# CATS-FAT-Pyro.net
KiCad netlist of a schematic drawn in Altium Designer
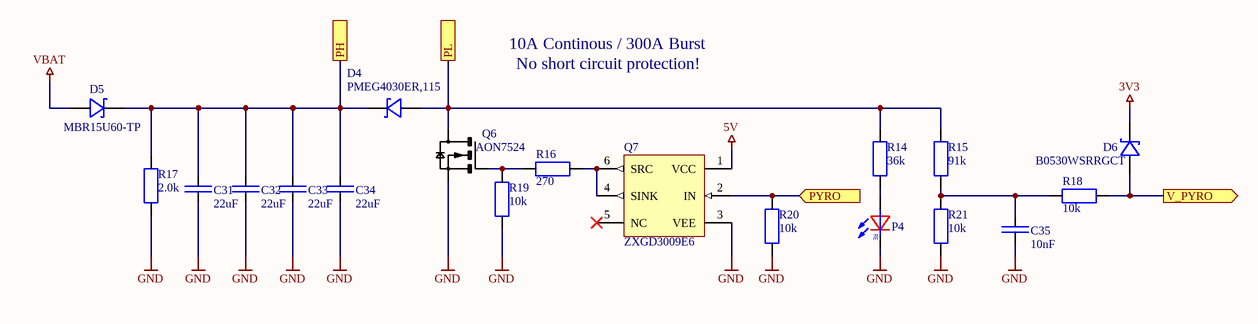
[diagram p0: CATS-FAT-Pyro.SchDoc]

(export (version "E")
  (design (tool "Eeschema 10.0.6"))
  (components
    (comp (ref "C31")
      (value "22uF")
      (footprint "SMD Keramikkondensator 0805")
      (description "SMD Ceramic Capacitor E6")
      (libsource (lib "Ceramic Capacitors-E6") (part "E6 - 22uF"))
    )
    (comp (ref "C32")
      (value "22uF")
      (footprint "SMD Keramikkondensator 0805")
      (description "SMD Ceramic Capacitor E6")
      (libsource (lib "Ceramic Capacitors-E6") (part "E6 - 22uF"))
    )
    (comp (ref "C33")
      (value "22uF")
      (footprint "SMD Keramikkondensator 0805")
      (description "SMD Ceramic Capacitor E6")
      (libsource (lib "Ceramic Capacitors-E6") (part "E6 - 22uF"))
    )
    (comp (ref "C34")
      (value "22uF")
      (footprint "SMD Keramikkondensator 0805")
      (description "SMD Ceramic Capacitor E6")
      (libsource (lib "Ceramic Capacitors-E6") (part "E6 - 22uF"))
    )
    (comp (ref "C35")
      (value "10nF")
      (footprint "SMD Keramikkondensator 0603")
      (description "SMD Ceramic Capacitor E6")
      (libsource (lib "Ceramic Capacitors-E6") (part "E6 - 10nF"))
    )
    (comp (ref "D4")
      (value "PMEG4030ER,115")
      (footprint "SMD Diode SOD-123")
      (description "Diode Schottky 3A Surface Mount CFP3")
      (libsource (lib "Diodes") (part "PMEG4030ER,115"))
    )
    (comp (ref "D5")
      (value "MBR15U60-TP")
      (footprint "SMD Diode TO-277")
      (description "Diode Schottky 15A Surface Mount TO-277-3")
      (libsource (lib "Diodes") (part "MBR15U60-TP"))
    )
    (comp (ref "D6")
      (value "B0530WSRRGCT")
      (footprint "SMD Diode SOD-323F")
      (description "200mW, 0.47V Schottky Barrier Diode")
      (libsource (lib "Diodes") (part "B0530WSRRGCT"))
    )
    (comp (ref "P4")
      (value "LED")
      (footprint "SMD LED 0603")
      (description "Color LED")
      (libsource (lib "Diodes") (part "LED"))
    )
    (comp (ref "Q6")
      (value "AON7524")
      (footprint "SMD MOSFET DFN 3x3 EP")
      (description "N-Channel 30V 25A (Ta), 28A (Tc) 3.1W (Ta), 32W (Tc) Surface Mount 8-DFN (3x3)")
      (libsource (lib "Electronic Switches") (part "AON7524"))
    )
    (comp (ref "Q7")
      (value "ZXGD3009E6")
      (footprint "SMD IC SOT-23-6")
      (description "Low-Side Gate Driver IC Non-Inverting SOT-26")
      (libsource (lib "Electronic Switches") (part "ZXGD3009E6"))
    )
    (comp (ref "R14")
      (value "36k")
      (footprint "SMD Widerstand 0603")
      (description "SMD Chip Resistor E24")
      (libsource (lib "Resistors-E24") (part "E24 - 36k"))
    )
    (comp (ref "R15")
      (value "91k")
      (footprint "SMD Widerstand 0603")
      (description "SMD Chip Resistor E24")
      (libsource (lib "Resistors-E24") (part "E24 - 91k"))
    )
    (comp (ref "R16")
      (value "270")
      (footprint "SMD Widerstand 0603")
      (description "SMD Chip Resistor E24")
      (libsource (lib "Resistors-E24") (part "E24 - 270"))
    )
    (comp (ref "R17")
      (value "2.0k")
      (footprint "SMD Widerstand 0603")
      (description "SMD Chip Resistor E24")
      (libsource (lib "Resistors-E24") (part "E24 - 2.0k"))
    )
    (comp (ref "R18")
      (value "10k")
      (footprint "SMD Widerstand 0603")
      (description "SMD Chip Resistor E24")
      (libsource (lib "Resistors-E24") (part "E24 - 10k"))
    )
    (comp (ref "R19")
      (value "10k")
      (footprint "SMD Widerstand 0603")
      (description "SMD Chip Resistor E24")
      (libsource (lib "") (part "E24 - 10k_1"))
    )
    (comp (ref "R20")
      (value "10k")
      (footprint "SMD Widerstand 0603")
      (description "SMD Chip Resistor E24")
      (libsource (lib "") (part "E24 - 10k_1"))
    )
    (comp (ref "R21")
      (value "10k")
      (footprint "SMD Widerstand 0603")
      (description "SMD Chip Resistor E24")
      (libsource (lib "") (part "E24 - 10k_1"))
    )
  )
  (nets
    (net (code "1") (name "/PH") (class "Default")
      (node (ref "C31") (pin "2") (pinfunction "2_2") (pintype "passive"))
      (node (ref "C32") (pin "2") (pinfunction "2_2") (pintype "passive"))
      (node (ref "C33") (pin "2") (pinfunction "2_2") (pintype "passive"))
      (node (ref "C34") (pin "2") (pinfunction "2_2") (pintype "passive"))
      (node (ref "D4") (pin "K") (pinfunction "K_K") (pintype "passive"))
      (node (ref "D5") (pin "K") (pinfunction "K_K") (pintype "passive"))
      (node (ref "R17") (pin "2") (pinfunction "2_2") (pintype "passive"))
    )
    (net (code "2") (name "/PL") (class "Default")
      (node (ref "D4") (pin "A") (pinfunction "A_A") (pintype "passive"))
      (node (ref "Q6") (pin "D") (pinfunction "D_D") (pintype "passive"))
      (node (ref "R14") (pin "2") (pinfunction "2_2") (pintype "passive"))
      (node (ref "R15") (pin "2") (pinfunction "2_2") (pintype "passive"))
    )
    (net (code "3") (name "/PYRO") (class "Default")
      (node (ref "Q7") (pin "2") (pinfunction "IN_2") (pintype "input"))
      (node (ref "R20") (pin "2") (pinfunction "2_2") (pintype "passive"))
    )
    (net (code "4") (name "/V_PYRO") (class "Default")
      (node (ref "D6") (pin "A") (pinfunction "A_A") (pintype "passive"))
      (node (ref "R18") (pin "1") (pinfunction "1_1") (pintype "passive"))
    )
    (net (code "5") (name "3V3") (class "Default")
      (node (ref "D6") (pin "K") (pinfunction "K_K") (pintype "passive"))
    )
    (net (code "6") (name "5V") (class "Default")
      (node (ref "Q7") (pin "1") (pinfunction "VCC_1") (pintype "passive"))
    )
    (net (code "7") (name "GND") (class "Default")
      (node (ref "C31") (pin "1") (pinfunction "1_1") (pintype "passive"))
      (node (ref "C32") (pin "1") (pinfunction "1_1") (pintype "passive"))
      (node (ref "C33") (pin "1") (pinfunction "1_1") (pintype "passive"))
      (node (ref "C34") (pin "1") (pinfunction "1_1") (pintype "passive"))
      (node (ref "C35") (pin "1") (pinfunction "1_1") (pintype "passive"))
      (node (ref "P4") (pin "K") (pinfunction "K_K") (pintype "passive"))
      (node (ref "Q6") (pin "S") (pinfunction "S_S") (pintype "passive"))
      (node (ref "Q7") (pin "3") (pinfunction "VEE_3") (pintype "passive"))
      (node (ref "R17") (pin "1") (pinfunction "1_1") (pintype "passive"))
      (node (ref "R19") (pin "1") (pinfunction "1_1") (pintype "passive"))
      (node (ref "R20") (pin "1") (pinfunction "1_1") (pintype "passive"))
      (node (ref "R21") (pin "1") (pinfunction "1_1") (pintype "passive"))
    )
    (net (code "8") (name "Net-(C35-Pad2)") (class "Default")
      (node (ref "C35") (pin "2") (pinfunction "2_2") (pintype "passive"))
      (node (ref "R15") (pin "1") (pinfunction "1_1") (pintype "passive"))
      (node (ref "R18") (pin "2") (pinfunction "2_2") (pintype "passive"))
      (node (ref "R21") (pin "2") (pinfunction "2_2") (pintype "passive"))
    )
    (net (code "9") (name "Net-(P4-PadA)") (class "Default")
      (node (ref "P4") (pin "A") (pinfunction "A_A") (pintype "passive"))
      (node (ref "R14") (pin "1") (pinfunction "1_1") (pintype "passive"))
    )
    (net (code "10") (name "Net-(Q6-PadG)") (class "Default")
      (node (ref "Q6") (pin "G") (pinfunction "G_G") (pintype "passive"))
      (node (ref "R16") (pin "1") (pinfunction "1_1") (pintype "passive"))
      (node (ref "R19") (pin "2") (pinfunction "2_2") (pintype "passive"))
    )
    (net (code "11") (name "Net-(Q7-SINK)") (class "Default")
      (node (ref "Q7") (pin "4") (pinfunction "SINK_4") (pintype "output"))
      (node (ref "Q7") (pin "6") (pinfunction "SRC_6") (pintype "output"))
      (node (ref "R16") (pin "2") (pinfunction "2_2") (pintype "passive"))
    )
    (net (code "12") (name "VBAT") (class "Default")
      (node (ref "D5") (pin "A") (pinfunction "A_A") (pintype "passive"))
    )
    (net (code "13") (name "unconnected-(Q7-NC-Pad5)") (class "Default")
      (node (ref "Q7") (pin "5") (pinfunction "NC_5") (pintype "passive+no_connect"))
    )
  )
)
